# Breadboard-NRF24L01.net
KiCad netlist of a schematic drawn in EAGLE
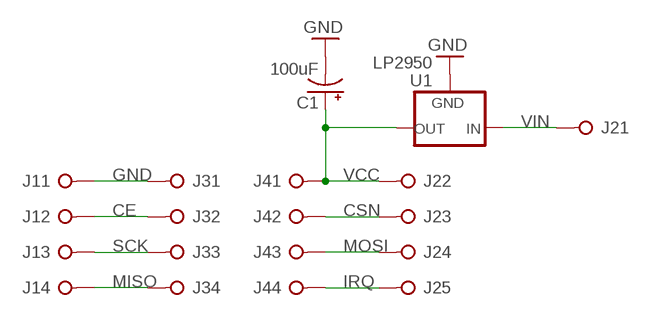
[diagram p0: schematic, sheet 1]

(export (version "E")
  (design (tool "Eeschema 10.0.6"))
  (components
    (comp (ref "C1")
      (value "100uF")
      (footprint "eagle-import:CAP-POL-2.5-6")
      (libsource (lib "eagle-import") (part "CAP-POL-2.5-6"))
    )
    (comp (ref "J1")
      (value "PINHD-1X4")
      (footprint "eagle-import:1X04")
      (libsource (lib "eagle-import") (part "PINHD-1X4"))
    )
    (comp (ref "J2")
      (value "PINHD-1X5")
      (footprint "eagle-import:1X05")
      (libsource (lib "eagle-import") (part "PINHD-1X5"))
    )
    (comp (ref "J3")
      (value "PINHD-1X4")
      (footprint "eagle-import:1X04")
      (libsource (lib "eagle-import") (part "PINHD-1X4"))
    )
    (comp (ref "J4")
      (value "PINHD-1X4")
      (footprint "eagle-import:1X04")
      (libsource (lib "eagle-import") (part "PINHD-1X4"))
    )
    (comp (ref "U1")
      (value "LP2950")
      (footprint "eagle-import:TO92-INLINE")
      (libsource (lib "eagle-import") (part "LP2950"))
    )
  )
  (nets
    (net (code "1") (name "/CE") (class "Default")
      (node (ref "J1") (pin "2") (pinfunction "KL_2") (pintype "passive"))
      (node (ref "J3") (pin "2") (pinfunction "KL_2") (pintype "passive"))
    )
    (net (code "2") (name "/CSN") (class "Default")
      (node (ref "J2") (pin "3") (pinfunction "KL_3") (pintype "passive"))
      (node (ref "J4") (pin "2") (pinfunction "KL_2") (pintype "passive"))
    )
    (net (code "3") (name "/IRQ") (class "Default")
      (node (ref "J2") (pin "5") (pinfunction "KL_5") (pintype "passive"))
      (node (ref "J4") (pin "4") (pinfunction "KL_4") (pintype "passive"))
    )
    (net (code "4") (name "/MISO") (class "Default")
      (node (ref "J1") (pin "4") (pinfunction "KL_4") (pintype "passive"))
      (node (ref "J3") (pin "4") (pinfunction "KL_4") (pintype "passive"))
    )
    (net (code "5") (name "/MOSI") (class "Default")
      (node (ref "J2") (pin "4") (pinfunction "KL_4") (pintype "passive"))
      (node (ref "J4") (pin "3") (pinfunction "KL_3") (pintype "passive"))
    )
    (net (code "6") (name "/SCK") (class "Default")
      (node (ref "J1") (pin "3") (pinfunction "KL_3") (pintype "passive"))
      (node (ref "J3") (pin "3") (pinfunction "KL_3") (pintype "passive"))
    )
    (net (code "7") (name "/VCC") (class "Default")
      (node (ref "C1") (pin "+") (pinfunction "+_+") (pintype "passive"))
      (node (ref "J2") (pin "2") (pinfunction "KL_2") (pintype "passive"))
      (node (ref "J4") (pin "1") (pinfunction "KL_1") (pintype "passive"))
      (node (ref "U1") (pin "1") (pinfunction "OUT_1") (pintype "passive"))
    )
    (net (code "8") (name "/VIN") (class "Default")
      (node (ref "J2") (pin "1") (pinfunction "KL_1") (pintype "passive"))
      (node (ref "U1") (pin "3") (pinfunction "IN_3") (pintype "input"))
    )
    (net (code "9") (name "GND") (class "Default")
      (node (ref "C1") (pin "-") (pinfunction "-_-") (pintype "passive"))
      (node (ref "J1") (pin "1") (pinfunction "KL_1") (pintype "passive"))
      (node (ref "J3") (pin "1") (pinfunction "KL_1") (pintype "passive"))
      (node (ref "U1") (pin "2") (pinfunction "GND_2") (pintype "input"))
    )
  )
)
